# heating-controller.net
KiCad netlist of a schematic drawn in EAGLE
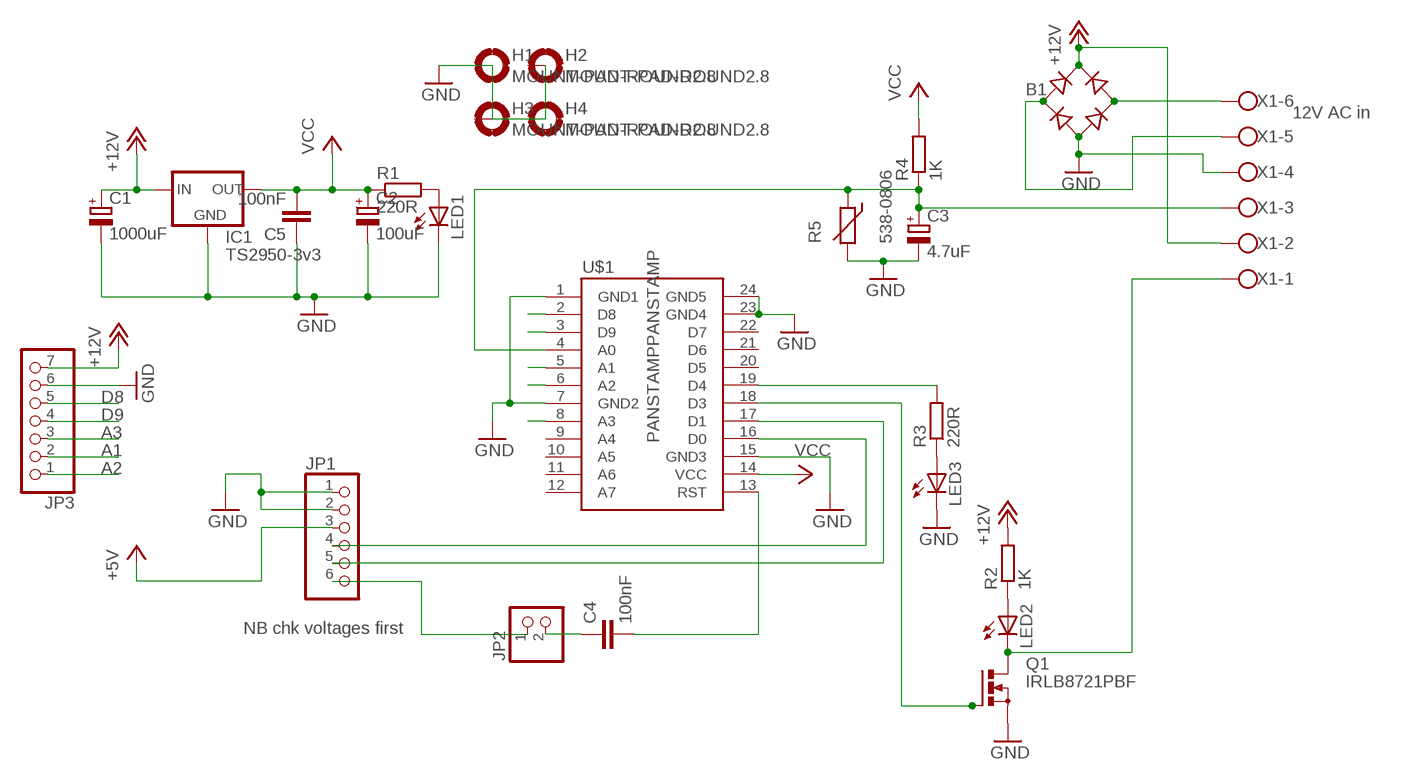
[diagram p0: schematic, sheet 1]

(export (version "E")
  (design (tool "Eeschema 10.0.6"))
  (components
    (comp (ref "B1")
      (value "B-DIL")
      (footprint "eagle-import:B-DIL")
      (libsource (lib "eagle-import") (part "B-DIL"))
    )
    (comp (ref "C1")
      (value "1000uF")
      (footprint "eagle-import:E3,5-10")
      (libsource (lib "eagle-import") (part "CPOL-EUE3.5-10"))
    )
    (comp (ref "C2")
      (value "100uF")
      (footprint "eagle-import:E3,5-10")
      (libsource (lib "eagle-import") (part "CPOL-EUE3.5-10"))
    )
    (comp (ref "C3")
      (value "4.7uF")
      (footprint "eagle-import:E3,5-10")
      (libsource (lib "eagle-import") (part "CPOL-EUE3.5-10"))
    )
    (comp (ref "C4")
      (value "100nF")
      (footprint "eagle-import:C050-024X044")
      (libsource (lib "eagle-import") (part "C-EU050-024X044"))
    )
    (comp (ref "C5")
      (value "100nF")
      (footprint "eagle-import:C050-024X044")
      (libsource (lib "eagle-import") (part "C-EU050-024X044"))
    )
    (comp (ref "H1")
      (value "MOUNT-PAD-ROUND2.8")
      (footprint "eagle-import:2,8-PAD")
      (libsource (lib "eagle-import") (part "MOUNT-PAD-ROUND2.8"))
    )
    (comp (ref "H2")
      (value "MOUNT-PAD-ROUND2.8")
      (footprint "eagle-import:2,8-PAD")
      (libsource (lib "eagle-import") (part "MOUNT-PAD-ROUND2.8"))
    )
    (comp (ref "H3")
      (value "MOUNT-PAD-ROUND2.8")
      (footprint "eagle-import:2,8-PAD")
      (libsource (lib "eagle-import") (part "MOUNT-PAD-ROUND2.8"))
    )
    (comp (ref "H4")
      (value "MOUNT-PAD-ROUND2.8")
      (footprint "eagle-import:2,8-PAD")
      (libsource (lib "eagle-import") (part "MOUNT-PAD-ROUND2.8"))
    )
    (comp (ref "IC1")
      (value "TS2950-3v3")
      (footprint "eagle-import:TO92")
      (libsource (lib "eagle-import") (part "LP2950?ACZ-3.0"))
    )
    (comp (ref "JP1")
      (value "PINHD-1X6")
      (footprint "eagle-import:1X06")
      (libsource (lib "eagle-import") (part "PINHD-1X6"))
    )
    (comp (ref "JP2")
      (value "PINHD-1X2")
      (footprint "eagle-import:1X02")
      (libsource (lib "eagle-import") (part "PINHD-1X2"))
    )
    (comp (ref "JP3")
      (value "PINHD-1X7")
      (footprint "eagle-import:1X07")
      (libsource (lib "eagle-import") (part "PINHD-1X7"))
    )
    (comp (ref "LED1")
      (value "LED3MM")
      (footprint "eagle-import:LED3MM")
      (libsource (lib "eagle-import") (part "LED3MM"))
    )
    (comp (ref "LED2")
      (value "LED3MM")
      (footprint "eagle-import:LED3MM")
      (libsource (lib "eagle-import") (part "LED3MM"))
    )
    (comp (ref "LED3")
      (value "LED3MM")
      (footprint "eagle-import:LED3MM")
      (libsource (lib "eagle-import") (part "LED3MM"))
    )
    (comp (ref "Q1")
      (value "IRLB8721PBF")
      (footprint "eagle-import:TO220BV")
      (libsource (lib "eagle-import") (part "PMOSFET_NTO220BV"))
    )
    (comp (ref "R1")
      (value "220R")
      (footprint "eagle-import:0207_7")
      (libsource (lib "eagle-import") (part "R-EU_0207/7"))
    )
    (comp (ref "R2")
      (value "1K")
      (footprint "eagle-import:0207_7")
      (libsource (lib "eagle-import") (part "R-EU_0207/7"))
    )
    (comp (ref "R3")
      (value "220R")
      (footprint "eagle-import:0207_7")
      (libsource (lib "eagle-import") (part "R-EU_0207/7"))
    )
    (comp (ref "R4")
      (value "1K")
      (footprint "eagle-import:0207_7")
      (libsource (lib "eagle-import") (part "R-EU_0207/7"))
    )
    (comp (ref "R5")
      (value "538-0806")
      (footprint "eagle-import:RS-2,5")
      (libsource (lib "eagle-import") (part "THERMISTOR-2,5"))
    )
    (comp (ref "U$1")
      (value "PANSTAMPPANSTAMP")
      (footprint "eagle-import:DIL24-6")
      (libsource (lib "eagle-import") (part "PANSTAMPPANSTAMP"))
    )
    (comp (ref "X1")
      (value "W237-6")
      (footprint "eagle-import:W237-6")
      (libsource (lib "eagle-import") (part "W237-6"))
    )
  )
  (nets
    (net (code "1") (name "+5V") (class "Default")
      (node (ref "JP1") (pin "3") (pinfunction "3_3") (pintype "passive"))
    )
    (net (code "2") (name "+12V") (class "Default")
      (node (ref "B1") (pin "+") (pinfunction "+_+") (pintype "passive"))
      (node (ref "C1") (pin "+") (pinfunction "+_+") (pintype "passive"))
      (node (ref "IC1") (pin "3") (pinfunction "IN_3") (pintype "input"))
      (node (ref "JP3") (pin "7") (pinfunction "7_7") (pintype "passive"))
      (node (ref "R2") (pin "2") (pinfunction "2_2") (pintype "passive"))
      (node (ref "X1") (pin "2") (pinfunction "KL_2") (pintype "passive"))
    )
    (net (code "3") (name "/A1") (class "Default")
      (node (ref "JP3") (pin "2") (pinfunction "2_2") (pintype "passive"))
      (node (ref "U$1") (pin "5") (pinfunction "A1_5") (pintype "bidirectional"))
    )
    (net (code "4") (name "/A2") (class "Default")
      (node (ref "JP3") (pin "1") (pinfunction "1_1") (pintype "passive"))
      (node (ref "U$1") (pin "6") (pinfunction "A2_6") (pintype "bidirectional"))
    )
    (net (code "5") (name "/A3") (class "Default")
      (node (ref "JP3") (pin "3") (pinfunction "3_3") (pintype "passive"))
      (node (ref "U$1") (pin "8") (pinfunction "A3_8") (pintype "bidirectional"))
    )
    (net (code "6") (name "/D8") (class "Default")
      (node (ref "JP3") (pin "5") (pinfunction "5_5") (pintype "passive"))
      (node (ref "U$1") (pin "2") (pinfunction "D8_2") (pintype "bidirectional"))
    )
    (net (code "7") (name "/D9") (class "Default")
      (node (ref "JP3") (pin "4") (pinfunction "4_4") (pintype "passive"))
      (node (ref "U$1") (pin "3") (pinfunction "D9_3") (pintype "bidirectional"))
    )
    (net (code "8") (name "GND") (class "Default")
      (node (ref "B1") (pin "-") (pinfunction "-_-") (pintype "passive"))
      (node (ref "C1") (pin "-") (pinfunction "-_-") (pintype "passive"))
      (node (ref "C2") (pin "-") (pinfunction "-_-") (pintype "passive"))
      (node (ref "C3") (pin "-") (pinfunction "-_-") (pintype "passive"))
      (node (ref "C5") (pin "1") (pinfunction "1_1") (pintype "passive"))
      (node (ref "IC1") (pin "2") (pinfunction "GND_2") (pintype "input"))
      (node (ref "JP1") (pin "1") (pinfunction "1_1") (pintype "passive"))
      (node (ref "JP1") (pin "2") (pinfunction "2_2") (pintype "passive"))
      (node (ref "JP3") (pin "6") (pinfunction "6_6") (pintype "passive"))
      (node (ref "LED1") (pin "K") (pinfunction "C_K") (pintype "passive"))
      (node (ref "LED3") (pin "K") (pinfunction "C_K") (pintype "passive"))
      (node (ref "Q1") (pin "S") (pinfunction "S_S") (pintype "passive"))
      (node (ref "R5") (pin "2") (pinfunction "2_2") (pintype "passive"))
      (node (ref "U$1") (pin "1") (pinfunction "GND1_1") (pintype "power_in"))
      (node (ref "U$1") (pin "15") (pinfunction "GND3_15") (pintype "power_in"))
      (node (ref "U$1") (pin "23") (pinfunction "GND4_23") (pintype "power_in"))
      (node (ref "U$1") (pin "24") (pinfunction "GND5_24") (pintype "power_in"))
      (node (ref "U$1") (pin "7") (pinfunction "GND2_7") (pintype "power_in"))
      (node (ref "X1") (pin "4") (pinfunction "KL_4") (pintype "passive"))
    )
    (net (code "9") (name "Net-(C4-Pad1)") (class "Default")
      (node (ref "C4") (pin "1") (pinfunction "1_1") (pintype "passive"))
      (node (ref "JP2") (pin "2") (pinfunction "2_2") (pintype "passive"))
    )
    (net (code "10") (name "Net-(JP1-Pad6)") (class "Default")
      (node (ref "JP1") (pin "6") (pinfunction "6_6") (pintype "passive"))
      (node (ref "JP2") (pin "1") (pinfunction "1_1") (pintype "passive"))
    )
    (net (code "11") (name "Net-(LED1-PadA)") (class "Default")
      (node (ref "LED1") (pin "A") (pinfunction "A_A") (pintype "passive"))
      (node (ref "R1") (pin "2") (pinfunction "2_2") (pintype "passive"))
    )
    (net (code "12") (name "Net-(LED2-C)") (class "Default")
      (node (ref "LED2") (pin "K") (pinfunction "C_K") (pintype "passive"))
      (node (ref "Q1") (pin "D") (pinfunction "D_D") (pintype "passive"))
      (node (ref "X1") (pin "1") (pinfunction "KL_1") (pintype "passive"))
    )
    (net (code "13") (name "Net-(LED2-PadA)") (class "Default")
      (node (ref "LED2") (pin "A") (pinfunction "A_A") (pintype "passive"))
      (node (ref "R2") (pin "1") (pinfunction "1_1") (pintype "passive"))
    )
    (net (code "14") (name "Net-(LED3-PadA)") (class "Default")
      (node (ref "LED3") (pin "A") (pinfunction "A_A") (pintype "passive"))
      (node (ref "R3") (pin "1") (pinfunction "1_1") (pintype "passive"))
    )
    (net (code "15") (name "Net-(U$1-A0)") (class "Default")
      (node (ref "C3") (pin "+") (pinfunction "+_+") (pintype "passive"))
      (node (ref "R4") (pin "1") (pinfunction "1_1") (pintype "passive"))
      (node (ref "R5") (pin "1") (pinfunction "1_1") (pintype "passive"))
      (node (ref "U$1") (pin "4") (pinfunction "A0_4") (pintype "bidirectional"))
      (node (ref "X1") (pin "3") (pinfunction "KL_3") (pintype "passive"))
    )
    (net (code "16") (name "Net-(U$1-D0)") (class "Default")
      (node (ref "JP1") (pin "4") (pinfunction "4_4") (pintype "passive"))
      (node (ref "U$1") (pin "16") (pinfunction "D0_16") (pintype "bidirectional"))
    )
    (net (code "17") (name "Net-(U$1-D1)") (class "Default")
      (node (ref "JP1") (pin "5") (pinfunction "5_5") (pintype "passive"))
      (node (ref "U$1") (pin "17") (pinfunction "D1_17") (pintype "bidirectional"))
    )
    (net (code "18") (name "Net-(U$1-D3)") (class "Default")
      (node (ref "Q1") (pin "G") (pinfunction "G_G") (pintype "passive"))
      (node (ref "U$1") (pin "18") (pinfunction "D3_18") (pintype "bidirectional"))
    )
    (net (code "19") (name "Net-(U$1-D4)") (class "Default")
      (node (ref "R3") (pin "2") (pinfunction "2_2") (pintype "passive"))
      (node (ref "U$1") (pin "19") (pinfunction "D4_19") (pintype "bidirectional"))
    )
    (net (code "20") (name "Net-(U$1-RST)") (class "Default")
      (node (ref "C4") (pin "2") (pinfunction "2_2") (pintype "passive"))
      (node (ref "U$1") (pin "13") (pinfunction "RST_13") (pintype "input"))
    )
    (net (code "21") (name "Net-(X1E-KL)") (class "Default")
      (node (ref "B1") (pin "AC2") (pinfunction "AC2_AC2") (pintype "passive"))
      (node (ref "X1") (pin "5") (pinfunction "KL_5") (pintype "passive"))
    )
    (net (code "22") (name "Net-(X1F-KL)") (class "Default")
      (node (ref "B1") (pin "AC1") (pinfunction "AC1_AC1") (pintype "passive"))
      (node (ref "X1") (pin "6") (pinfunction "KL_6") (pintype "passive"))
    )
    (net (code "23") (name "VCC") (class "Default")
      (node (ref "C2") (pin "+") (pinfunction "+_+") (pintype "passive"))
      (node (ref "C5") (pin "2") (pinfunction "2_2") (pintype "passive"))
      (node (ref "IC1") (pin "1") (pinfunction "OUT_1") (pintype "passive"))
      (node (ref "R1") (pin "1") (pinfunction "1_1") (pintype "passive"))
      (node (ref "R4") (pin "2") (pinfunction "2_2") (pintype "passive"))
      (node (ref "U$1") (pin "14") (pinfunction "VCC_14") (pintype "power_in"))
    )
    (net (code "24") (name "unconnected-(H1-MOUNT-PadB2,8)") (class "Default")
      (node (ref "H1") (pin "B2,8") (pinfunction "MOUNT_B2,8") (pintype "passive"))
    )
    (net (code "25") (name "unconnected-(H2-MOUNT-PadB2,8)") (class "Default")
      (node (ref "H2") (pin "B2,8") (pinfunction "MOUNT_B2,8") (pintype "passive"))
    )
    (net (code "26") (name "unconnected-(H3-MOUNT-PadB2,8)") (class "Default")
      (node (ref "H3") (pin "B2,8") (pinfunction "MOUNT_B2,8") (pintype "passive"))
    )
    (net (code "27") (name "unconnected-(H4-MOUNT-PadB2,8)") (class "Default")
      (node (ref "H4") (pin "B2,8") (pinfunction "MOUNT_B2,8") (pintype "passive"))
    )
    (net (code "28") (name "unconnected-(U$1-A4-Pad9)") (class "Default")
      (node (ref "U$1") (pin "9") (pinfunction "A4_9") (pintype "bidirectional"))
    )
    (net (code "29") (name "unconnected-(U$1-A5-Pad10)") (class "Default")
      (node (ref "U$1") (pin "10") (pinfunction "A5_10") (pintype "bidirectional"))
    )
    (net (code "30") (name "unconnected-(U$1-A6-Pad11)") (class "Default")
      (node (ref "U$1") (pin "11") (pinfunction "A6_11") (pintype "bidirectional"))
    )
    (net (code "31") (name "unconnected-(U$1-A7-Pad12)") (class "Default")
      (node (ref "U$1") (pin "12") (pinfunction "A7_12") (pintype "bidirectional"))
    )
    (net (code "32") (name "unconnected-(U$1-D5-Pad20)") (class "Default")
      (node (ref "U$1") (pin "20") (pinfunction "D5_20") (pintype "bidirectional"))
    )
    (net (code "33") (name "unconnected-(U$1-D6-Pad21)") (class "Default")
      (node (ref "U$1") (pin "21") (pinfunction "D6_21") (pintype "bidirectional"))
    )
    (net (code "34") (name "unconnected-(U$1-D7-Pad22)") (class "Default")
      (node (ref "U$1") (pin "22") (pinfunction "D7_22") (pintype "bidirectional"))
    )
  )
)
